# rota.net
KiCad netlist of a schematic drawn in Altium Designer
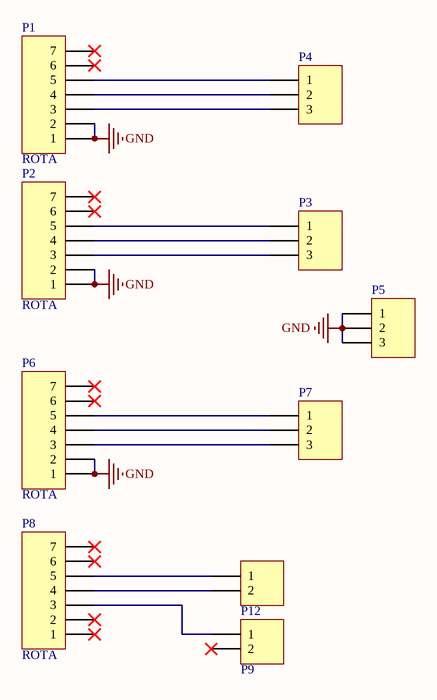
[diagram p0: rota.SchDoc]

(export (version "E")
  (design (tool "Eeschema 10.0.6"))
  (components
    (comp (ref "P1")
      (value "ROTA")
      (footprint "rotation_key")
      (description "Header, 7-Pin")
      (fields (field (name "PUBLISHER") "Altium Limited"))
      (libsource (lib "Miscellaneous Connectors") (part "Header 7"))
    )
    (comp (ref "P2")
      (value "ROTA")
      (footprint "rotation_key")
      (description "Header, 7-Pin")
      (fields (field (name "PUBLISHER") "Altium Limited"))
      (libsource (lib "Miscellaneous Connectors") (part "Header 7"))
    )
    (comp (ref "P3")
      (value "Header 3")
      (footprint "ROTA-3PIN")
      (description "Header, 3-Pin")
      (fields (field (name "PUBLISHER") "Altium Limited"))
      (libsource (lib "Miscellaneous Connectors") (part "Header 3"))
    )
    (comp (ref "P4")
      (value "Header 3")
      (footprint "ROTA-3PIN")
      (description "Header, 3-Pin")
      (fields (field (name "PUBLISHER") "Altium Limited"))
      (libsource (lib "Miscellaneous Connectors") (part "Header 3"))
    )
    (comp (ref "P5")
      (value "Header 3")
      (footprint "ROTA-3PIN")
      (description "Header, 3-Pin")
      (fields (field (name "PUBLISHER") "Altium Limited"))
      (libsource (lib "Miscellaneous Connectors") (part "Header 3"))
    )
    (comp (ref "P6")
      (value "ROTA")
      (footprint "rotation_key")
      (description "Header, 7-Pin")
      (fields (field (name "PUBLISHER") "Altium Limited"))
      (libsource (lib "Miscellaneous Connectors") (part "Header 7"))
    )
    (comp (ref "P7")
      (value "Header 3")
      (footprint "ROTA-3PIN")
      (description "Header, 3-Pin")
      (fields (field (name "PUBLISHER") "Altium Limited"))
      (libsource (lib "Miscellaneous Connectors") (part "Header 3"))
    )
    (comp (ref "P8")
      (value "ROTA")
      (footprint "rotation_key")
      (description "Header, 7-Pin")
      (fields (field (name "PUBLISHER") "Altium Limited"))
      (libsource (lib "Miscellaneous Connectors") (part "Header 7"))
    )
    (comp (ref "P9")
      (value "Header 2")
      (footprint "ROTA-2PIN")
      (description "Header, 2-Pin")
      (fields (field (name "PUBLISHER") "Altium Limited"))
      (libsource (lib "Miscellaneous Connectors") (part "Header 2"))
    )
    (comp (ref "P12")
      (value "Header 2")
      (footprint "ROTA-2PIN")
      (description "Header, 2-Pin")
      (fields (field (name "PUBLISHER") "Altium Limited"))
      (libsource (lib "Miscellaneous Connectors") (part "Header 2"))
    )
  )
  (nets
    (net (code "1") (name "GND") (class "Default")
      (node (ref "P1") (pin "1") (pinfunction "1_1") (pintype "passive"))
      (node (ref "P1") (pin "2") (pinfunction "2_2") (pintype "passive"))
      (node (ref "P2") (pin "1") (pinfunction "1_1") (pintype "passive"))
      (node (ref "P2") (pin "2") (pinfunction "2_2") (pintype "passive"))
      (node (ref "P5") (pin "1") (pinfunction "1_1") (pintype "passive"))
      (node (ref "P5") (pin "2") (pinfunction "2_2") (pintype "passive"))
      (node (ref "P5") (pin "3") (pinfunction "3_3") (pintype "passive"))
      (node (ref "P6") (pin "1") (pinfunction "1_1") (pintype "passive"))
      (node (ref "P6") (pin "2") (pinfunction "2_2") (pintype "passive"))
    )
    (net (code "2") (name "Net-(P1-Pad3)") (class "Default")
      (node (ref "P1") (pin "3") (pinfunction "3_3") (pintype "passive"))
      (node (ref "P4") (pin "3") (pinfunction "3_3") (pintype "passive"))
    )
    (net (code "3") (name "Net-(P1-Pad4)") (class "Default")
      (node (ref "P1") (pin "4") (pinfunction "4_4") (pintype "passive"))
      (node (ref "P4") (pin "2") (pinfunction "2_2") (pintype "passive"))
    )
    (net (code "4") (name "Net-(P1-Pad5)") (class "Default")
      (node (ref "P1") (pin "5") (pinfunction "5_5") (pintype "passive"))
      (node (ref "P4") (pin "1") (pinfunction "1_1") (pintype "passive"))
    )
    (net (code "5") (name "Net-(P2-Pad3)") (class "Default")
      (node (ref "P2") (pin "3") (pinfunction "3_3") (pintype "passive"))
      (node (ref "P3") (pin "3") (pinfunction "3_3") (pintype "passive"))
    )
    (net (code "6") (name "Net-(P2-Pad4)") (class "Default")
      (node (ref "P2") (pin "4") (pinfunction "4_4") (pintype "passive"))
      (node (ref "P3") (pin "2") (pinfunction "2_2") (pintype "passive"))
    )
    (net (code "7") (name "Net-(P2-Pad5)") (class "Default")
      (node (ref "P2") (pin "5") (pinfunction "5_5") (pintype "passive"))
      (node (ref "P3") (pin "1") (pinfunction "1_1") (pintype "passive"))
    )
    (net (code "8") (name "Net-(P6-Pad3)") (class "Default")
      (node (ref "P6") (pin "3") (pinfunction "3_3") (pintype "passive"))
      (node (ref "P7") (pin "3") (pinfunction "3_3") (pintype "passive"))
    )
    (net (code "9") (name "Net-(P6-Pad4)") (class "Default")
      (node (ref "P6") (pin "4") (pinfunction "4_4") (pintype "passive"))
      (node (ref "P7") (pin "2") (pinfunction "2_2") (pintype "passive"))
    )
    (net (code "10") (name "Net-(P6-Pad5)") (class "Default")
      (node (ref "P6") (pin "5") (pinfunction "5_5") (pintype "passive"))
      (node (ref "P7") (pin "1") (pinfunction "1_1") (pintype "passive"))
    )
    (net (code "11") (name "Net-(P8-Pad3)") (class "Default")
      (node (ref "P8") (pin "3") (pinfunction "3_3") (pintype "passive"))
      (node (ref "P9") (pin "1") (pinfunction "1_1") (pintype "passive"))
    )
    (net (code "12") (name "Net-(P12-Pad1)") (class "Default")
      (node (ref "P12") (pin "1") (pinfunction "1_1") (pintype "passive"))
      (node (ref "P8") (pin "5") (pinfunction "5_5") (pintype "passive"))
    )
    (net (code "13") (name "Net-(P12-Pad2)") (class "Default")
      (node (ref "P12") (pin "2") (pinfunction "2_2") (pintype "passive"))
      (node (ref "P8") (pin "4") (pinfunction "4_4") (pintype "passive"))
    )
    (net (code "14") (name "unconnected-(P1-Pad6)") (class "Default")
      (node (ref "P1") (pin "6") (pinfunction "6_6") (pintype "passive+no_connect"))
    )
    (net (code "15") (name "unconnected-(P1-Pad7)") (class "Default")
      (node (ref "P1") (pin "7") (pinfunction "7_7") (pintype "passive+no_connect"))
    )
    (net (code "16") (name "unconnected-(P2-Pad6)") (class "Default")
      (node (ref "P2") (pin "6") (pinfunction "6_6") (pintype "passive+no_connect"))
    )
    (net (code "17") (name "unconnected-(P2-Pad7)") (class "Default")
      (node (ref "P2") (pin "7") (pinfunction "7_7") (pintype "passive+no_connect"))
    )
    (net (code "18") (name "unconnected-(P6-Pad6)") (class "Default")
      (node (ref "P6") (pin "6") (pinfunction "6_6") (pintype "passive+no_connect"))
    )
    (net (code "19") (name "unconnected-(P6-Pad7)") (class "Default")
      (node (ref "P6") (pin "7") (pinfunction "7_7") (pintype "passive+no_connect"))
    )
    (net (code "20") (name "unconnected-(P8-Pad1)") (class "Default")
      (node (ref "P8") (pin "1") (pinfunction "1_1") (pintype "passive+no_connect"))
    )
    (net (code "21") (name "unconnected-(P8-Pad2)") (class "Default")
      (node (ref "P8") (pin "2") (pinfunction "2_2") (pintype "passive+no_connect"))
    )
    (net (code "22") (name "unconnected-(P8-Pad6)") (class "Default")
      (node (ref "P8") (pin "6") (pinfunction "6_6") (pintype "passive+no_connect"))
    )
    (net (code "23") (name "unconnected-(P8-Pad7)") (class "Default")
      (node (ref "P8") (pin "7") (pinfunction "7_7") (pintype "passive+no_connect"))
    )
    (net (code "24") (name "unconnected-(P9-Pad2)") (class "Default")
      (node (ref "P9") (pin "2") (pinfunction "2_2") (pintype "passive+no_connect"))
    )
  )
)
